# Power.net
KiCad netlist of a schematic drawn in Altium Designer
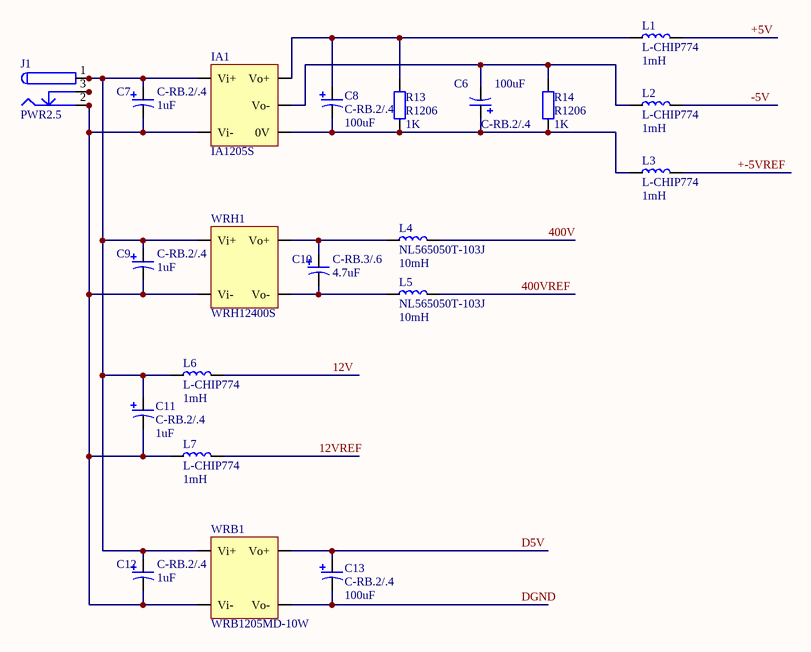
[diagram p0: Power.SchDoc]

(export (version "E")
  (design (tool "Eeschema 10.0.6"))
  (components
    (comp (ref "C6")
      (value "C-RB.2/.4")
      (footprint "RB.2/.4")
      (description "Capacitor")
      (fields (field (name "ALTIUM_VALUE") "100uF"))
      (libsource (lib "UFDLib") (part "C-RB.2/.4"))
    )
    (comp (ref "C7")
      (value "C-RB.2/.4")
      (footprint "RB.2/.4")
      (description "Capacitor")
      (fields (field (name "ALTIUM_VALUE") "1uF"))
      (libsource (lib "UFDLib") (part "C-RB.2/.4"))
    )
    (comp (ref "C8")
      (value "C-RB.2/.4")
      (footprint "RB.2/.4")
      (description "Capacitor")
      (fields (field (name "ALTIUM_VALUE") "100uF"))
      (libsource (lib "UFDLib") (part "C-RB.2/.4"))
    )
    (comp (ref "C9")
      (value "C-RB.2/.4")
      (footprint "RB.2/.4")
      (description "Capacitor")
      (fields (field (name "ALTIUM_VALUE") "1uF"))
      (libsource (lib "UFDLib") (part "C-RB.2/.4"))
    )
    (comp (ref "C10")
      (value "C-RB.3/.6")
      (footprint "RB.3/.6")
      (description "Capacitor")
      (fields (field (name "ALTIUM_VALUE") "4.7uF"))
      (libsource (lib "UFDLib") (part "C-RB.3/.6"))
    )
    (comp (ref "C11")
      (value "C-RB.2/.4")
      (footprint "RB.2/.4")
      (description "Capacitor")
      (fields (field (name "ALTIUM_VALUE") "1uF"))
      (libsource (lib "UFDLib") (part "C-RB.2/.4"))
    )
    (comp (ref "C12")
      (value "C-RB.2/.4")
      (footprint "RB.2/.4")
      (description "Capacitor")
      (fields (field (name "ALTIUM_VALUE") "1uF"))
      (libsource (lib "UFDLib") (part "C-RB.2/.4"))
    )
    (comp (ref "C13")
      (value "C-RB.2/.4")
      (footprint "RB.2/.4")
      (description "Capacitor")
      (fields (field (name "ALTIUM_VALUE") "100uF"))
      (libsource (lib "UFDLib") (part "C-RB.2/.4"))
    )
    (comp (ref "IA1")
      (value "IA1205S")
      (footprint "IA1205S")
      (description "IA1205S,12V to +5V,-5V")
      (libsource (lib "UFDLib") (part "IA1205S"))
    )
    (comp (ref "J1")
      (value "PWR2.5")
      (footprint "KLD-0202")
      (description "Low Voltage Power Supply Connector")
      (fields (field (name "PUBLISHER") "Altium Limited"))
      (libsource (lib "Miscellaneous Connectors") (part "PWR2.5"))
    )
    (comp (ref "L1")
      (value "L-CHIP774")
      (footprint "INDUCTOR070704")
      (description "Chip Inductor, 7*7*4")
      (fields (field (name "ALTIUM_VALUE") "1mH"))
      (libsource (lib "UFDLib") (part "Inductor070704"))
    )
    (comp (ref "L2")
      (value "L-CHIP774")
      (footprint "INDUCTOR070704")
      (description "Chip Inductor, 7*7*4")
      (fields (field (name "ALTIUM_VALUE") "1mH"))
      (libsource (lib "UFDLib") (part "Inductor070704"))
    )
    (comp (ref "L3")
      (value "L-CHIP774")
      (footprint "INDUCTOR070704")
      (description "Chip Inductor, 7*7*4")
      (fields (field (name "ALTIUM_VALUE") "1mH"))
      (libsource (lib "UFDLib") (part "Inductor070704"))
    )
    (comp (ref "L4")
      (value "NL565050T-103J")
      (footprint "NL565050T")
      (description "NL565050T, 10mH, 150 ohm")
      (fields (field (name "ALTIUM_VALUE") "10mH"))
      (libsource (lib "UFDLib") (part "NL565050T-103J"))
    )
    (comp (ref "L5")
      (value "NL565050T-103J")
      (footprint "NL565050T")
      (description "NL565050T, 10mH, 150 ohm")
      (fields (field (name "ALTIUM_VALUE") "10mH"))
      (libsource (lib "UFDLib") (part "NL565050T-103J"))
    )
    (comp (ref "L6")
      (value "L-CHIP774")
      (footprint "INDUCTOR070704")
      (description "Chip Inductor, 7*7*4")
      (fields (field (name "ALTIUM_VALUE") "1mH"))
      (libsource (lib "UFDLib") (part "Inductor070704"))
    )
    (comp (ref "L7")
      (value "L-CHIP774")
      (footprint "INDUCTOR070704")
      (description "Chip Inductor, 7*7*4")
      (fields (field (name "ALTIUM_VALUE") "1mH"))
      (libsource (lib "UFDLib") (part "Inductor070704"))
    )
    (comp (ref "R13")
      (value "R1206")
      (footprint "1206")
      (description "Resistor, 1206, 1/4W")
      (fields (field (name "ALTIUM_VALUE") "1K"))
      (libsource (lib "UFDLib") (part "R1206"))
    )
    (comp (ref "R14")
      (value "R1206")
      (footprint "1206")
      (description "Resistor, 1206, 1/4W")
      (fields (field (name "ALTIUM_VALUE") "1K"))
      (libsource (lib "UFDLib") (part "R1206"))
    )
    (comp (ref "WRB1")
      (value "WRB1205MD-10W")
      (footprint "WRB1205MD-10W")
      (description "WRB1205MD-10W,12V-5V")
      (libsource (lib "UFDLib") (part "WRB1205MD-10W"))
    )
    (comp (ref "WRH1")
      (value "WRH12400S")
      (footprint "WRH12400S")
      (description "WRH12400S,12V-400V")
      (libsource (lib "UFDLib") (part "WRH12400S"))
    )
  )
  (nets
    (net (code "1") (name "/+-5VREF") (class "Default")
      (node (ref "L3") (pin "2") (pinfunction "2_2") (pintype "passive"))
    )
    (net (code "2") (name "/+5V") (class "Default")
      (node (ref "L1") (pin "2") (pinfunction "2_2") (pintype "passive"))
    )
    (net (code "3") (name "/-5V") (class "Default")
      (node (ref "L2") (pin "2") (pinfunction "2_2") (pintype "passive"))
    )
    (net (code "4") (name "/12V") (class "Default")
      (node (ref "L6") (pin "2") (pinfunction "2_2") (pintype "passive"))
    )
    (net (code "5") (name "/12VREF") (class "Default")
      (node (ref "L7") (pin "2") (pinfunction "2_2") (pintype "passive"))
    )
    (net (code "6") (name "/400V") (class "Default")
      (node (ref "L4") (pin "2") (pinfunction "2_2") (pintype "passive"))
    )
    (net (code "7") (name "/400VREF") (class "Default")
      (node (ref "L5") (pin "2") (pinfunction "2_2") (pintype "passive"))
    )
    (net (code "8") (name "/D5V") (class "Default")
      (node (ref "C13") (pin "2") (pinfunction "b_2") (pintype "passive"))
      (node (ref "WRB1") (pin "3") (pinfunction "Vo+_3") (pintype "passive"))
    )
    (net (code "9") (name "/DGND") (class "Default")
      (node (ref "C13") (pin "1") (pinfunction "a_1") (pintype "passive"))
      (node (ref "WRB1") (pin "5") (pinfunction "Vo-_5") (pintype "passive"))
    )
    (net (code "10") (name "Net-(C6-a)") (class "Default")
      (node (ref "C6") (pin "1") (pinfunction "a_1") (pintype "passive"))
      (node (ref "IA1") (pin "9") (pinfunction "Vo-_9") (pintype "passive"))
      (node (ref "L2") (pin "1") (pinfunction "1_1") (pintype "passive"))
      (node (ref "R14") (pin "2") (pinfunction "b_2") (pintype "passive"))
    )
    (net (code "11") (name "Net-(C6-b)") (class "Default")
      (node (ref "C6") (pin "2") (pinfunction "b_2") (pintype "passive"))
      (node (ref "C8") (pin "1") (pinfunction "a_1") (pintype "passive"))
      (node (ref "IA1") (pin "10") (pinfunction "0V_10") (pintype "passive"))
      (node (ref "L3") (pin "1") (pinfunction "1_1") (pintype "passive"))
      (node (ref "R13") (pin "1") (pinfunction "a_1") (pintype "passive"))
      (node (ref "R14") (pin "1") (pinfunction "a_1") (pintype "passive"))
    )
    (net (code "12") (name "Net-(C8-b)") (class "Default")
      (node (ref "C8") (pin "2") (pinfunction "b_2") (pintype "passive"))
      (node (ref "IA1") (pin "7") (pinfunction "Vo+_7") (pintype "passive"))
      (node (ref "L1") (pin "1") (pinfunction "1_1") (pintype "passive"))
      (node (ref "R13") (pin "2") (pinfunction "b_2") (pintype "passive"))
    )
    (net (code "13") (name "Net-(C10-a)") (class "Default")
      (node (ref "C10") (pin "1") (pinfunction "a_1") (pintype "passive"))
      (node (ref "L5") (pin "1") (pinfunction "1_1") (pintype "passive"))
      (node (ref "WRH1") (pin "5") (pinfunction "Vo-_5") (pintype "passive"))
    )
    (net (code "14") (name "Net-(C10-b)") (class "Default")
      (node (ref "C10") (pin "2") (pinfunction "b_2") (pintype "passive"))
      (node (ref "L4") (pin "1") (pinfunction "1_1") (pintype "passive"))
      (node (ref "WRH1") (pin "3") (pinfunction "Vo+_3") (pintype "passive"))
    )
    (net (code "15") (name "Net-(C11-a)") (class "Default")
      (node (ref "C11") (pin "1") (pinfunction "a_1") (pintype "passive"))
      (node (ref "C12") (pin "1") (pinfunction "a_1") (pintype "passive"))
      (node (ref "C7") (pin "1") (pinfunction "a_1") (pintype "passive"))
      (node (ref "C9") (pin "1") (pinfunction "a_1") (pintype "passive"))
      (node (ref "IA1") (pin "2") (pinfunction "Vi-_2") (pintype "passive"))
      (node (ref "J1") (pin "2") (pinfunction "2_2") (pintype "power_in"))
      (node (ref "J1") (pin "2A") (pinfunction "2A_2A") (pintype "power_in"))
      (node (ref "J1") (pin "2B") (pinfunction "2B_2B") (pintype "power_in"))
      (node (ref "L7") (pin "1") (pinfunction "1_1") (pintype "passive"))
      (node (ref "WRB1") (pin "2") (pinfunction "Vi-_2") (pintype "passive"))
      (node (ref "WRH1") (pin "2") (pinfunction "Vi-_2") (pintype "passive"))
    )
    (net (code "16") (name "Net-(C11-b)") (class "Default")
      (node (ref "C11") (pin "2") (pinfunction "b_2") (pintype "passive"))
      (node (ref "C12") (pin "2") (pinfunction "b_2") (pintype "passive"))
      (node (ref "C7") (pin "2") (pinfunction "b_2") (pintype "passive"))
      (node (ref "C9") (pin "2") (pinfunction "b_2") (pintype "passive"))
      (node (ref "IA1") (pin "1") (pinfunction "Vi+_1") (pintype "passive"))
      (node (ref "J1") (pin "1") (pinfunction "1_1") (pintype "power_in"))
      (node (ref "J1") (pin "1A") (pinfunction "1A_1A") (pintype "power_in"))
      (node (ref "J1") (pin "1B") (pinfunction "1B_1B") (pintype "power_in"))
      (node (ref "L6") (pin "1") (pinfunction "1_1") (pintype "passive"))
      (node (ref "WRB1") (pin "1") (pinfunction "Vi+_1") (pintype "passive"))
      (node (ref "WRH1") (pin "1") (pinfunction "Vi+_1") (pintype "passive"))
    )
    (net (code "17") (name "Net-(J1-Pad3)") (class "Default")
      (node (ref "J1") (pin "3") (pinfunction "3_3") (pintype "power_in"))
      (node (ref "J1") (pin "3A") (pinfunction "3A_3A") (pintype "power_in"))
      (node (ref "J1") (pin "3B") (pinfunction "3B_3B") (pintype "power_in"))
    )
  )
)
